# WifiDriverREV3.net
KiCad netlist of a schematic drawn in EAGLE
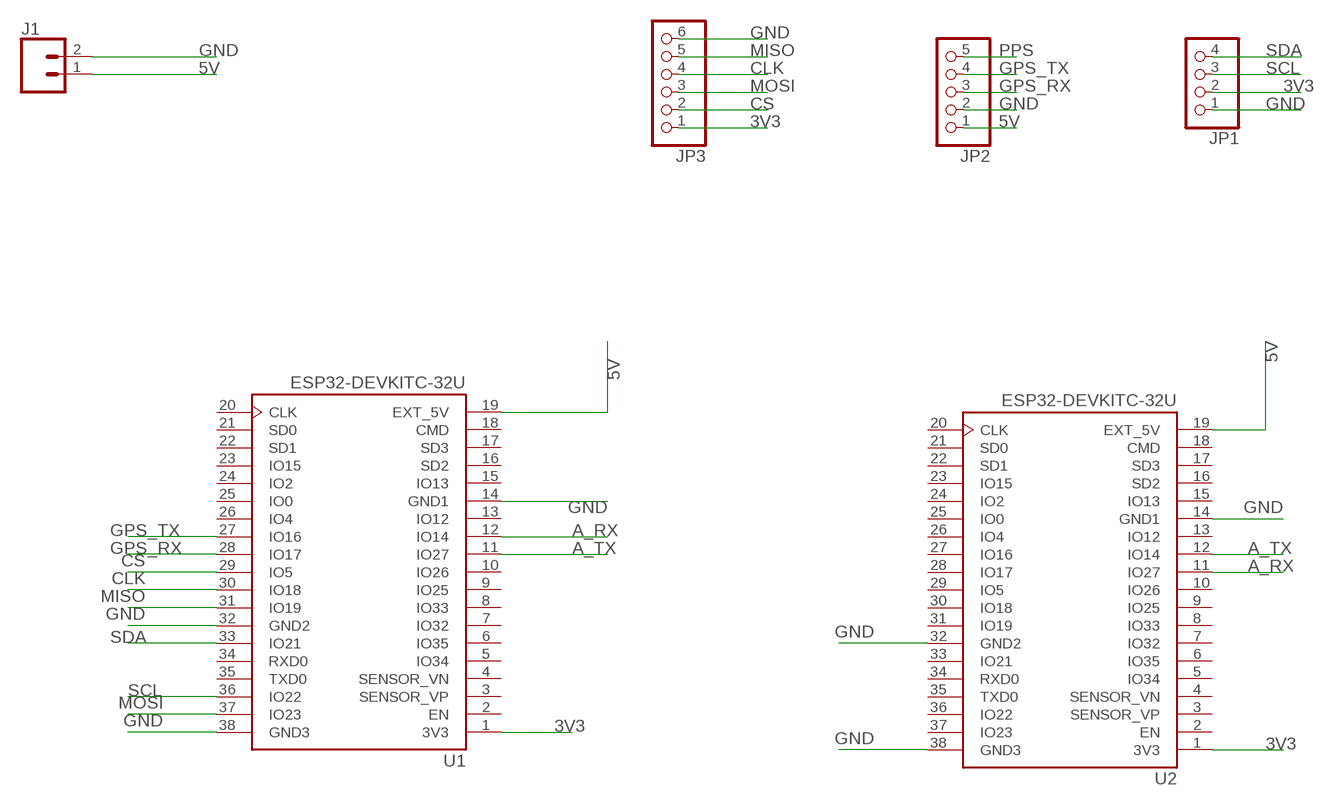
[diagram p0: schematic, sheet 1]

(export (version "E")
  (design (tool "Eeschema 10.0.6"))
  (components
    (comp (ref "J1")
      (value "CONN_023.5MM_LOCK")
      (footprint "eagle-import:SCREWTERMINAL-3.5MM-2_LOCK")
      (libsource (lib "eagle-import") (part "CONN_023.5MM_LOCK"))
    )
    (comp (ref "JP1")
      (value "PINHD-1X4")
      (footprint "eagle-import:1X04")
      (libsource (lib "eagle-import") (part "PINHD-1X4"))
    )
    (comp (ref "JP2")
      (value "PINHD-1X5")
      (footprint "eagle-import:1X05")
      (libsource (lib "eagle-import") (part "PINHD-1X5"))
    )
    (comp (ref "JP3")
      (value "PINHD-1X6")
      (footprint "eagle-import:1X06")
      (libsource (lib "eagle-import") (part "PINHD-1X6"))
    )
    (comp (ref "U1")
      (value "ESP32-DEVKITC-32U")
      (footprint "eagle-import:MODULE_ESP32-DEVKITC-32U")
      (fields (field (name "MF") "Espressif Systems"))
      (libsource (lib "eagle-import") (part "ESP32-DEVKITC-32U"))
    )
    (comp (ref "U2")
      (value "ESP32-DEVKITC-32U")
      (footprint "eagle-import:MODULE_ESP32-DEVKITC-32U")
      (fields (field (name "MF") "Espressif Systems"))
      (libsource (lib "eagle-import") (part "ESP32-DEVKITC-32U"))
    )
  )
  (nets
    (net (code "1") (name "/3V3") (class "Default")
      (node (ref "JP1") (pin "2") (pinfunction "2_2") (pintype "passive"))
      (node (ref "JP3") (pin "1") (pinfunction "1_1") (pintype "passive"))
      (node (ref "U1") (pin "1") (pinfunction "3V3_1") (pintype "power_in"))
      (node (ref "U2") (pin "1") (pinfunction "3V3_1") (pintype "power_in"))
    )
    (net (code "2") (name "/5V") (class "Default")
      (node (ref "J1") (pin "1") (pinfunction "1_1") (pintype "passive"))
      (node (ref "JP2") (pin "1") (pinfunction "1_1") (pintype "passive"))
      (node (ref "U1") (pin "19") (pinfunction "EXT_5V_19") (pintype "power_in"))
      (node (ref "U2") (pin "19") (pinfunction "EXT_5V_19") (pintype "power_in"))
    )
    (net (code "3") (name "/A_RX") (class "Default")
      (node (ref "U1") (pin "12") (pinfunction "IO14_12") (pintype "bidirectional"))
      (node (ref "U2") (pin "11") (pinfunction "IO27_11") (pintype "bidirectional"))
    )
    (net (code "4") (name "/A_TX") (class "Default")
      (node (ref "U1") (pin "11") (pinfunction "IO27_11") (pintype "bidirectional"))
      (node (ref "U2") (pin "12") (pinfunction "IO14_12") (pintype "bidirectional"))
    )
    (net (code "5") (name "/CLK") (class "Default")
      (node (ref "JP3") (pin "4") (pinfunction "4_4") (pintype "passive"))
      (node (ref "U1") (pin "30") (pinfunction "IO18_30") (pintype "bidirectional"))
    )
    (net (code "6") (name "/CS") (class "Default")
      (node (ref "JP3") (pin "2") (pinfunction "2_2") (pintype "passive"))
      (node (ref "U1") (pin "29") (pinfunction "IO5_29") (pintype "bidirectional"))
    )
    (net (code "7") (name "/GND") (class "Default")
      (node (ref "J1") (pin "2") (pinfunction "2_2") (pintype "passive"))
      (node (ref "JP1") (pin "1") (pinfunction "1_1") (pintype "passive"))
      (node (ref "JP2") (pin "2") (pinfunction "2_2") (pintype "passive"))
      (node (ref "JP3") (pin "6") (pinfunction "6_6") (pintype "passive"))
      (node (ref "U1") (pin "14") (pinfunction "GND1_14") (pintype "power_in"))
      (node (ref "U1") (pin "32") (pinfunction "GND2_32") (pintype "power_in"))
      (node (ref "U1") (pin "38") (pinfunction "GND3_38") (pintype "power_in"))
      (node (ref "U2") (pin "14") (pinfunction "GND1_14") (pintype "power_in"))
      (node (ref "U2") (pin "32") (pinfunction "GND2_32") (pintype "power_in"))
      (node (ref "U2") (pin "38") (pinfunction "GND3_38") (pintype "power_in"))
    )
    (net (code "8") (name "/GPS_RX") (class "Default")
      (node (ref "JP2") (pin "3") (pinfunction "3_3") (pintype "passive"))
      (node (ref "U1") (pin "28") (pinfunction "IO17_28") (pintype "bidirectional"))
    )
    (net (code "9") (name "/GPS_TX") (class "Default")
      (node (ref "JP2") (pin "4") (pinfunction "4_4") (pintype "passive"))
      (node (ref "U1") (pin "27") (pinfunction "IO16_27") (pintype "bidirectional"))
    )
    (net (code "10") (name "/MISO") (class "Default")
      (node (ref "JP3") (pin "5") (pinfunction "5_5") (pintype "passive"))
      (node (ref "U1") (pin "31") (pinfunction "IO19_31") (pintype "bidirectional"))
    )
    (net (code "11") (name "/MOSI") (class "Default")
      (node (ref "JP3") (pin "3") (pinfunction "3_3") (pintype "passive"))
      (node (ref "U1") (pin "37") (pinfunction "IO23_37") (pintype "bidirectional"))
    )
    (net (code "12") (name "/PPS") (class "Default")
      (node (ref "JP2") (pin "5") (pinfunction "5_5") (pintype "passive"))
    )
    (net (code "13") (name "/SCL") (class "Default")
      (node (ref "JP1") (pin "3") (pinfunction "3_3") (pintype "passive"))
      (node (ref "U1") (pin "36") (pinfunction "IO22_36") (pintype "bidirectional"))
    )
    (net (code "14") (name "/SDA") (class "Default")
      (node (ref "JP1") (pin "4") (pinfunction "4_4") (pintype "passive"))
      (node (ref "U1") (pin "33") (pinfunction "IO21_33") (pintype "bidirectional"))
    )
    (net (code "15") (name "unconnected-(U1-CLK-Pad20)") (class "Default")
      (node (ref "U1") (pin "20") (pinfunction "CLK_20") (pintype "input"))
    )
    (net (code "16") (name "unconnected-(U1-CMD-Pad18)") (class "Default")
      (node (ref "U1") (pin "18") (pinfunction "CMD_18") (pintype "bidirectional"))
    )
    (net (code "17") (name "unconnected-(U1-EN-Pad2)") (class "Default")
      (node (ref "U1") (pin "2") (pinfunction "EN_2") (pintype "input"))
    )
    (net (code "18") (name "unconnected-(U1-IO0-Pad25)") (class "Default")
      (node (ref "U1") (pin "25") (pinfunction "IO0_25") (pintype "bidirectional"))
    )
    (net (code "19") (name "unconnected-(U1-IO2-Pad24)") (class "Default")
      (node (ref "U1") (pin "24") (pinfunction "IO2_24") (pintype "bidirectional"))
    )
    (net (code "20") (name "unconnected-(U1-IO4-Pad26)") (class "Default")
      (node (ref "U1") (pin "26") (pinfunction "IO4_26") (pintype "bidirectional"))
    )
    (net (code "21") (name "unconnected-(U1-IO12-Pad13)") (class "Default")
      (node (ref "U1") (pin "13") (pinfunction "IO12_13") (pintype "bidirectional"))
    )
    (net (code "22") (name "unconnected-(U1-IO13-Pad15)") (class "Default")
      (node (ref "U1") (pin "15") (pinfunction "IO13_15") (pintype "bidirectional"))
    )
    (net (code "23") (name "unconnected-(U1-IO15-Pad23)") (class "Default")
      (node (ref "U1") (pin "23") (pinfunction "IO15_23") (pintype "bidirectional"))
    )
    (net (code "24") (name "unconnected-(U1-IO25-Pad9)") (class "Default")
      (node (ref "U1") (pin "9") (pinfunction "IO25_9") (pintype "bidirectional"))
    )
    (net (code "25") (name "unconnected-(U1-IO26-Pad10)") (class "Default")
      (node (ref "U1") (pin "10") (pinfunction "IO26_10") (pintype "bidirectional"))
    )
    (net (code "26") (name "unconnected-(U1-IO32-Pad7)") (class "Default")
      (node (ref "U1") (pin "7") (pinfunction "IO32_7") (pintype "bidirectional"))
    )
    (net (code "27") (name "unconnected-(U1-IO33-Pad8)") (class "Default")
      (node (ref "U1") (pin "8") (pinfunction "IO33_8") (pintype "bidirectional"))
    )
    (net (code "28") (name "unconnected-(U1-IO34-Pad5)") (class "Default")
      (node (ref "U1") (pin "5") (pinfunction "IO34_5") (pintype "bidirectional"))
    )
    (net (code "29") (name "unconnected-(U1-IO35-Pad6)") (class "Default")
      (node (ref "U1") (pin "6") (pinfunction "IO35_6") (pintype "bidirectional"))
    )
    (net (code "30") (name "unconnected-(U1-RXD0-Pad34)") (class "Default")
      (node (ref "U1") (pin "34") (pinfunction "RXD0_34") (pintype "input"))
    )
    (net (code "31") (name "unconnected-(U1-SD0-Pad21)") (class "Default")
      (node (ref "U1") (pin "21") (pinfunction "SD0_21") (pintype "bidirectional"))
    )
    (net (code "32") (name "unconnected-(U1-SD1-Pad22)") (class "Default")
      (node (ref "U1") (pin "22") (pinfunction "SD1_22") (pintype "bidirectional"))
    )
    (net (code "33") (name "unconnected-(U1-SD2-Pad16)") (class "Default")
      (node (ref "U1") (pin "16") (pinfunction "SD2_16") (pintype "bidirectional"))
    )
    (net (code "34") (name "unconnected-(U1-SD3-Pad17)") (class "Default")
      (node (ref "U1") (pin "17") (pinfunction "SD3_17") (pintype "bidirectional"))
    )
    (net (code "35") (name "unconnected-(U1-SENSOR_VN-Pad4)") (class "Default")
      (node (ref "U1") (pin "4") (pinfunction "SENSOR_VN_4") (pintype "input"))
    )
    (net (code "36") (name "unconnected-(U1-SENSOR_VP-Pad3)") (class "Default")
      (node (ref "U1") (pin "3") (pinfunction "SENSOR_VP_3") (pintype "input"))
    )
    (net (code "37") (name "unconnected-(U1-TXD0-Pad35)") (class "Default")
      (node (ref "U1") (pin "35") (pinfunction "TXD0_35") (pintype "output"))
    )
    (net (code "38") (name "unconnected-(U2-CLK-Pad20)") (class "Default")
      (node (ref "U2") (pin "20") (pinfunction "CLK_20") (pintype "input"))
    )
    (net (code "39") (name "unconnected-(U2-CMD-Pad18)") (class "Default")
      (node (ref "U2") (pin "18") (pinfunction "CMD_18") (pintype "bidirectional"))
    )
    (net (code "40") (name "unconnected-(U2-EN-Pad2)") (class "Default")
      (node (ref "U2") (pin "2") (pinfunction "EN_2") (pintype "input"))
    )
    (net (code "41") (name "unconnected-(U2-IO0-Pad25)") (class "Default")
      (node (ref "U2") (pin "25") (pinfunction "IO0_25") (pintype "bidirectional"))
    )
    (net (code "42") (name "unconnected-(U2-IO2-Pad24)") (class "Default")
      (node (ref "U2") (pin "24") (pinfunction "IO2_24") (pintype "bidirectional"))
    )
    (net (code "43") (name "unconnected-(U2-IO4-Pad26)") (class "Default")
      (node (ref "U2") (pin "26") (pinfunction "IO4_26") (pintype "bidirectional"))
    )
    (net (code "44") (name "unconnected-(U2-IO5-Pad29)") (class "Default")
      (node (ref "U2") (pin "29") (pinfunction "IO5_29") (pintype "bidirectional"))
    )
    (net (code "45") (name "unconnected-(U2-IO12-Pad13)") (class "Default")
      (node (ref "U2") (pin "13") (pinfunction "IO12_13") (pintype "bidirectional"))
    )
    (net (code "46") (name "unconnected-(U2-IO13-Pad15)") (class "Default")
      (node (ref "U2") (pin "15") (pinfunction "IO13_15") (pintype "bidirectional"))
    )
    (net (code "47") (name "unconnected-(U2-IO15-Pad23)") (class "Default")
      (node (ref "U2") (pin "23") (pinfunction "IO15_23") (pintype "bidirectional"))
    )
    (net (code "48") (name "unconnected-(U2-IO16-Pad27)") (class "Default")
      (node (ref "U2") (pin "27") (pinfunction "IO16_27") (pintype "bidirectional"))
    )
    (net (code "49") (name "unconnected-(U2-IO17-Pad28)") (class "Default")
      (node (ref "U2") (pin "28") (pinfunction "IO17_28") (pintype "bidirectional"))
    )
    (net (code "50") (name "unconnected-(U2-IO18-Pad30)") (class "Default")
      (node (ref "U2") (pin "30") (pinfunction "IO18_30") (pintype "bidirectional"))
    )
    (net (code "51") (name "unconnected-(U2-IO19-Pad31)") (class "Default")
      (node (ref "U2") (pin "31") (pinfunction "IO19_31") (pintype "bidirectional"))
    )
    (net (code "52") (name "unconnected-(U2-IO21-Pad33)") (class "Default")
      (node (ref "U2") (pin "33") (pinfunction "IO21_33") (pintype "bidirectional"))
    )
    (net (code "53") (name "unconnected-(U2-IO22-Pad36)") (class "Default")
      (node (ref "U2") (pin "36") (pinfunction "IO22_36") (pintype "bidirectional"))
    )
    (net (code "54") (name "unconnected-(U2-IO23-Pad37)") (class "Default")
      (node (ref "U2") (pin "37") (pinfunction "IO23_37") (pintype "bidirectional"))
    )
    (net (code "55") (name "unconnected-(U2-IO25-Pad9)") (class "Default")
      (node (ref "U2") (pin "9") (pinfunction "IO25_9") (pintype "bidirectional"))
    )
    (net (code "56") (name "unconnected-(U2-IO26-Pad10)") (class "Default")
      (node (ref "U2") (pin "10") (pinfunction "IO26_10") (pintype "bidirectional"))
    )
    (net (code "57") (name "unconnected-(U2-IO32-Pad7)") (class "Default")
      (node (ref "U2") (pin "7") (pinfunction "IO32_7") (pintype "bidirectional"))
    )
    (net (code "58") (name "unconnected-(U2-IO33-Pad8)") (class "Default")
      (node (ref "U2") (pin "8") (pinfunction "IO33_8") (pintype "bidirectional"))
    )
    (net (code "59") (name "unconnected-(U2-IO34-Pad5)") (class "Default")
      (node (ref "U2") (pin "5") (pinfunction "IO34_5") (pintype "bidirectional"))
    )
    (net (code "60") (name "unconnected-(U2-IO35-Pad6)") (class "Default")
      (node (ref "U2") (pin "6") (pinfunction "IO35_6") (pintype "bidirectional"))
    )
    (net (code "61") (name "unconnected-(U2-RXD0-Pad34)") (class "Default")
      (node (ref "U2") (pin "34") (pinfunction "RXD0_34") (pintype "input"))
    )
    (net (code "62") (name "unconnected-(U2-SD0-Pad21)") (class "Default")
      (node (ref "U2") (pin "21") (pinfunction "SD0_21") (pintype "bidirectional"))
    )
    (net (code "63") (name "unconnected-(U2-SD1-Pad22)") (class "Default")
      (node (ref "U2") (pin "22") (pinfunction "SD1_22") (pintype "bidirectional"))
    )
    (net (code "64") (name "unconnected-(U2-SD2-Pad16)") (class "Default")
      (node (ref "U2") (pin "16") (pinfunction "SD2_16") (pintype "bidirectional"))
    )
    (net (code "65") (name "unconnected-(U2-SD3-Pad17)") (class "Default")
      (node (ref "U2") (pin "17") (pinfunction "SD3_17") (pintype "bidirectional"))
    )
    (net (code "66") (name "unconnected-(U2-SENSOR_VN-Pad4)") (class "Default")
      (node (ref "U2") (pin "4") (pinfunction "SENSOR_VN_4") (pintype "input"))
    )
    (net (code "67") (name "unconnected-(U2-SENSOR_VP-Pad3)") (class "Default")
      (node (ref "U2") (pin "3") (pinfunction "SENSOR_VP_3") (pintype "input"))
    )
    (net (code "68") (name "unconnected-(U2-TXD0-Pad35)") (class "Default")
      (node (ref "U2") (pin "35") (pinfunction "TXD0_35") (pintype "output"))
    )
  )
)
